# ATTINY85.net
KiCad netlist of a schematic drawn in Altium Designer
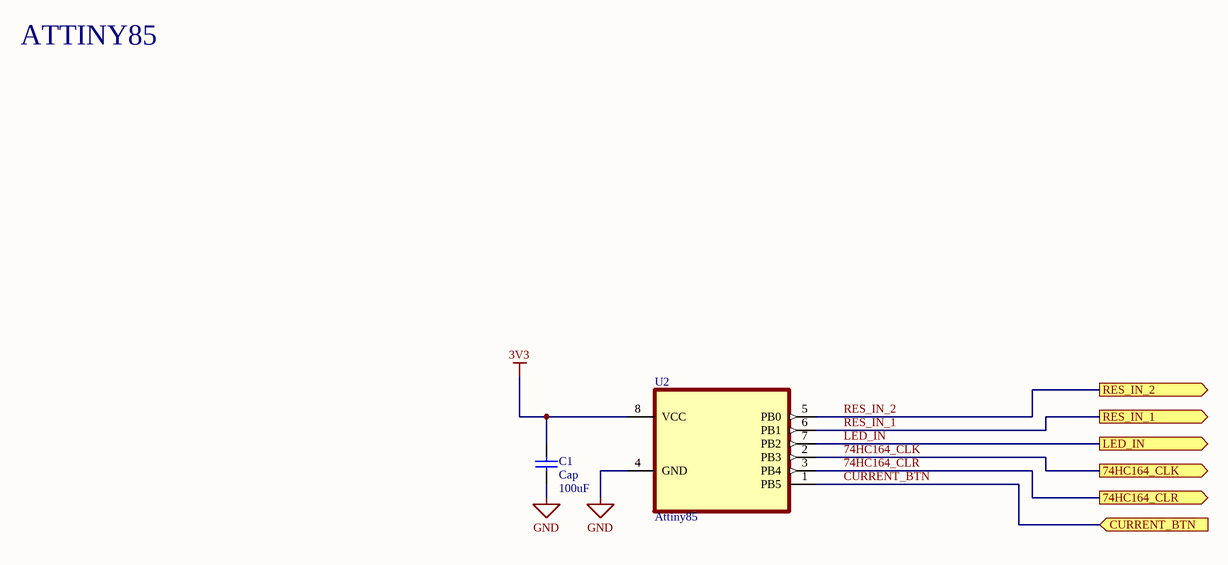
[diagram p0: ATTINY85.SchDoc]

(export (version "E")
  (design (tool "Eeschema 10.0.6"))
  (components
    (comp (ref "C1")
      (value "Cap")
      (footprint "RAD-0.3")
      (description "Capacitor")
      (fields (field (name "ALTIUM_VALUE") "100uF") (field (name "PUBLISHER") "Altium Limited"))
      (libsource (lib "Miscellaneous Devices") (part "Cap"))
    )
    (comp (ref "U2")
      (value "Attiny85")
      (footprint "SnapEDApcb:SOIC127P798X216-8N")
      (description "AVR ATtiny Microcontroller IC 8-Bit 20MHz 8KB _4K x 16_ FLASH 8-SOIC")
      (fields (field (name "MP") "ATTINY85-20SH") (field (name "MF") "Microchip"))
      (libsource (lib "main_schlib") (part "ATTINY85-20SH"))
    )
  )
  (nets
    (net (code "1") (name "/74HC164_CLK") (class "Default")
      (node (ref "U2") (pin "2") (pinfunction "PB3_2") (pintype "output"))
    )
    (net (code "2") (name "/74HC164_CLR") (class "Default")
      (node (ref "U2") (pin "3") (pinfunction "PB4_3") (pintype "output"))
    )
    (net (code "3") (name "/CURRENT_BTN") (class "Default")
      (node (ref "U2") (pin "1") (pinfunction "PB5_1") (pintype "passive"))
    )
    (net (code "4") (name "/LED_IN") (class "Default")
      (node (ref "U2") (pin "7") (pinfunction "PB2_7") (pintype "output"))
    )
    (net (code "5") (name "/RES_IN_1") (class "Default")
      (node (ref "U2") (pin "6") (pinfunction "PB1_6") (pintype "output"))
    )
    (net (code "6") (name "/RES_IN_2") (class "Default")
      (node (ref "U2") (pin "5") (pinfunction "PB0_5") (pintype "output"))
    )
    (net (code "7") (name "3V3") (class "Default")
      (node (ref "C1") (pin "2") (pinfunction "2_2") (pintype "passive"))
      (node (ref "U2") (pin "8") (pinfunction "VCC_8") (pintype "power_in"))
    )
    (net (code "8") (name "GND") (class "Default")
      (node (ref "C1") (pin "1") (pinfunction "1_1") (pintype "passive"))
      (node (ref "U2") (pin "4") (pinfunction "GND_4") (pintype "passive"))
    )
  )
)
